# generic_maxi_1.net
KiCad netlist of a schematic drawn in EAGLE
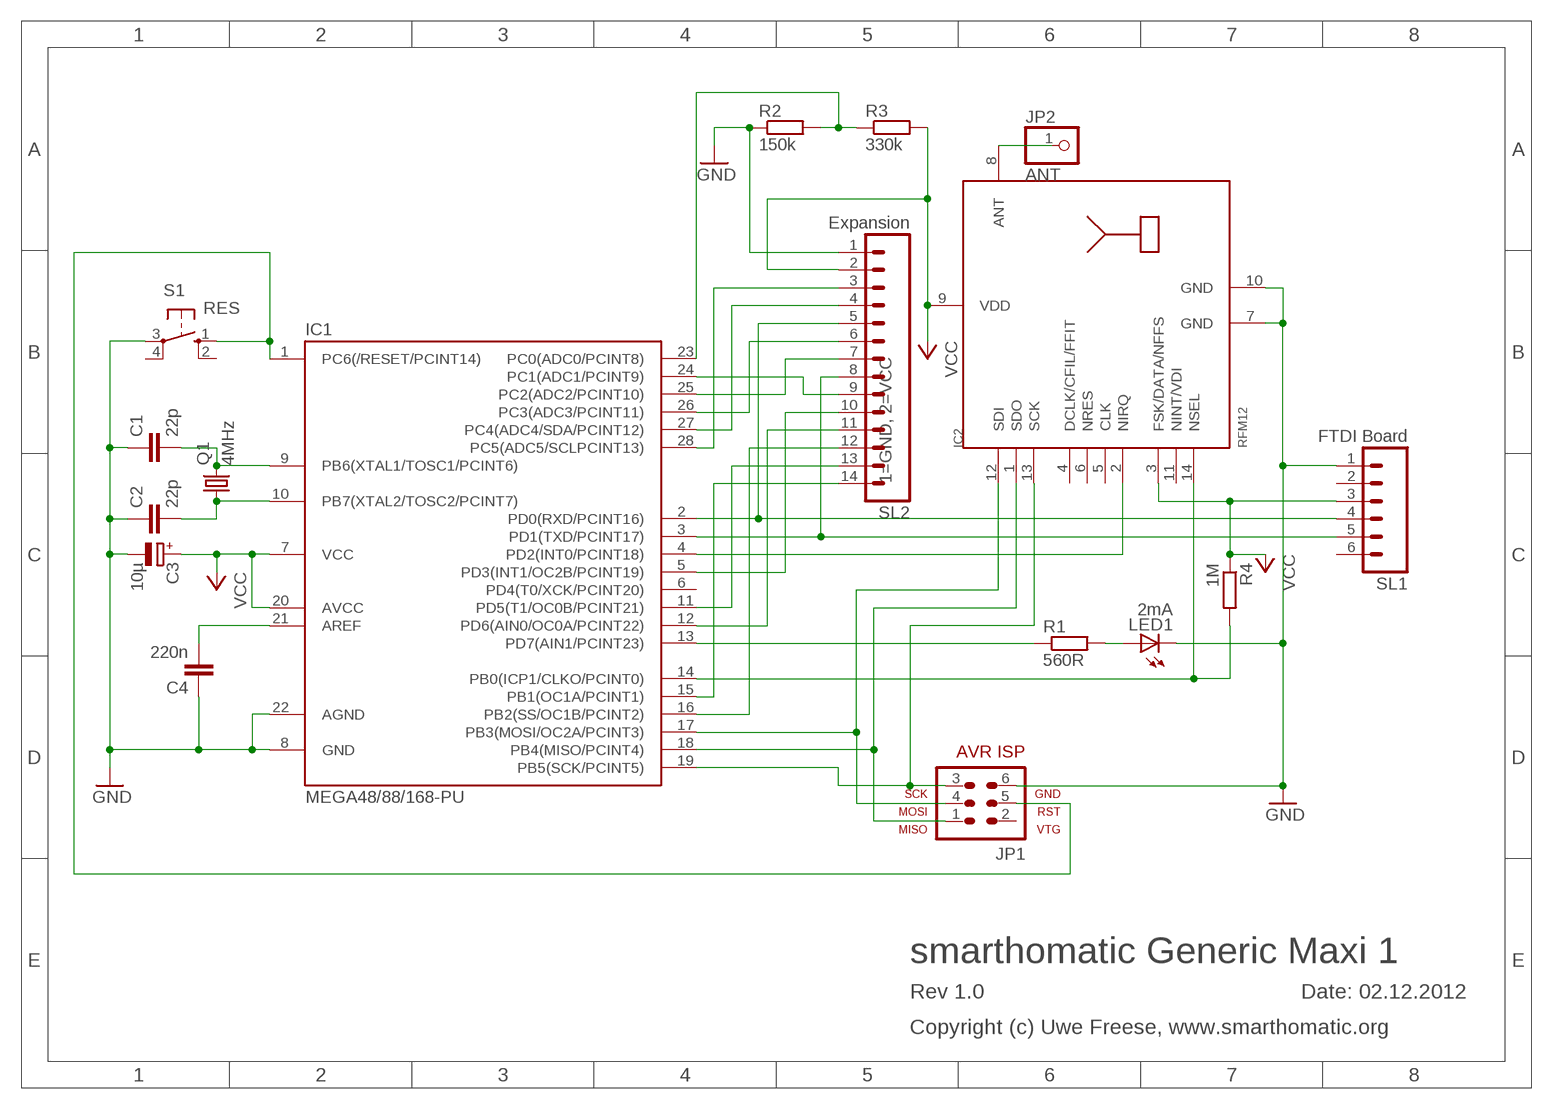
[diagram p0: schematic, sheet 1]

(export (version "E")
  (design (tool "Eeschema 10.0.6"))
  (components
    (comp (ref "C1")
      (value "22p")
      (footprint "eagle-import:C025-024X044")
      (libsource (lib "eagle-import") (part "C-EU025-024X044"))
    )
    (comp (ref "C2")
      (value "22p")
      (footprint "eagle-import:C025-024X044")
      (libsource (lib "eagle-import") (part "C-EU025-024X044"))
    )
    (comp (ref "C3")
      (value "10µ")
      (footprint "eagle-import:E1,8-4")
      (libsource (lib "eagle-import") (part "CPOL-EUE1.8-4"))
    )
    (comp (ref "C4")
      (value "220n")
      (footprint "eagle-import:C025-030X050")
      (libsource (lib "eagle-import") (part "C-EU025-030X050"))
    )
    (comp (ref "IC1")
      (value "MEGA48/88/168-PU")
      (footprint "eagle-import:DIL28-3")
      (libsource (lib "eagle-import") (part "MEGA48/88/168-PU"))
    )
    (comp (ref "IC2")
      (value "RFM12")
      (footprint "eagle-import:RFM")
      (libsource (lib "eagle-import") (part "RFM12"))
    )
    (comp (ref "JP1")
      (value "AVR-ISP-6")
      (footprint "eagle-import:AVR-ISP-6")
      (libsource (lib "eagle-import") (part "AVR-ISP-6"))
    )
    (comp (ref "JP2")
      (value "ANT")
      (footprint "eagle-import:1X01")
      (libsource (lib "eagle-import") (part "PINHD-1X1"))
    )
    (comp (ref "LED1")
      (value "2mA")
      (footprint "eagle-import:LED3MM")
      (libsource (lib "eagle-import") (part "LED3MM"))
    )
    (comp (ref "Q1")
      (value "4MHz")
      (footprint "eagle-import:HC49_S")
      (libsource (lib "eagle-import") (part "CRYSTALHC49S"))
    )
    (comp (ref "R1")
      (value "560R")
      (footprint "eagle-import:0207_7")
      (libsource (lib "eagle-import") (part "R-EU_0207/7"))
    )
    (comp (ref "R2")
      (value "150k")
      (footprint "eagle-import:0207_7")
      (libsource (lib "eagle-import") (part "R-EU_0207/7"))
    )
    (comp (ref "R3")
      (value "330k")
      (footprint "eagle-import:0207_7")
      (libsource (lib "eagle-import") (part "R-EU_0207/7"))
    )
    (comp (ref "R4")
      (value "1M")
      (footprint "eagle-import:0207_7")
      (libsource (lib "eagle-import") (part "R-EU_0207/7"))
    )
    (comp (ref "S1")
      (value "RES")
      (footprint "eagle-import:B3F-10XX")
      (fields (field (name "MPN") "B3F-1000"))
      (libsource (lib "eagle-import") (part "10-XX"))
    )
    (comp (ref "SL1")
      (value "FTDI Board")
      (footprint "eagle-import:06P")
      (libsource (lib "eagle-import") (part "M06"))
    )
    (comp (ref "SL2")
      (value "Expansion")
      (footprint "eagle-import:14P")
      (libsource (lib "eagle-import") (part "M14"))
    )
  )
  (nets
    (net (code "1") (name "GND") (class "Default")
      (node (ref "C1") (pin "1") (pinfunction "1_1") (pintype "passive"))
      (node (ref "C2") (pin "1") (pinfunction "1_1") (pintype "passive"))
      (node (ref "C3") (pin "-") (pinfunction "-_-") (pintype "passive"))
      (node (ref "C4") (pin "1") (pinfunction "1_1") (pintype "passive"))
      (node (ref "IC1") (pin "22") (pinfunction "AGND_22") (pintype "power_in"))
      (node (ref "IC1") (pin "8") (pinfunction "GND_8") (pintype "power_in"))
      (node (ref "IC2") (pin "10") (pinfunction "GND_10") (pintype "power_in"))
      (node (ref "IC2") (pin "7") (pinfunction "GND_7") (pintype "power_in"))
      (node (ref "JP1") (pin "6") (pinfunction "6_6") (pintype "passive"))
      (node (ref "LED1") (pin "K") (pinfunction "C_K") (pintype "passive"))
      (node (ref "R2") (pin "1") (pinfunction "1_1") (pintype "passive"))
      (node (ref "S1") (pin "3") (pinfunction "P_3") (pintype "passive"))
      (node (ref "SL1") (pin "1") (pinfunction "1_1") (pintype "passive"))
      (node (ref "SL2") (pin "1") (pinfunction "1_1") (pintype "passive"))
    )
    (net (code "2") (name "Net-(IC1-AREF)") (class "Default")
      (node (ref "C4") (pin "2") (pinfunction "2_2") (pintype "passive"))
      (node (ref "IC1") (pin "21") (pinfunction "AREF_21") (pintype "passive"))
    )
    (net (code "3") (name "Net-(IC1-PB0(ICP1{slash}CLKO{slash}PCINT0))") (class "Default")
      (node (ref "IC1") (pin "14") (pinfunction "PB0(ICP1/CLKO/PCINT0)_14") (pintype "bidirectional"))
      (node (ref "IC2") (pin "14") (pinfunction "NSEL_14") (pintype "bidirectional"))
      (node (ref "R4") (pin "2") (pinfunction "2_2") (pintype "passive"))
    )
    (net (code "4") (name "Net-(IC1-PB1(OC1A{slash}PCINT1))") (class "Default")
      (node (ref "IC1") (pin "15") (pinfunction "PB1(OC1A/PCINT1)_15") (pintype "bidirectional"))
      (node (ref "SL2") (pin "14") (pinfunction "14_14") (pintype "passive"))
    )
    (net (code "5") (name "Net-(IC1-PB2(SS{slash}OC1B{slash}PCINT2))") (class "Default")
      (node (ref "IC1") (pin "16") (pinfunction "PB2(SS/OC1B/PCINT2)_16") (pintype "bidirectional"))
      (node (ref "SL2") (pin "12") (pinfunction "12_12") (pintype "passive"))
    )
    (net (code "6") (name "Net-(IC1-PB3(MOSI{slash}OC2A{slash}PCINT3))") (class "Default")
      (node (ref "IC1") (pin "17") (pinfunction "PB3(MOSI/OC2A/PCINT3)_17") (pintype "bidirectional"))
      (node (ref "IC2") (pin "12") (pinfunction "SDI_12") (pintype "bidirectional"))
      (node (ref "JP1") (pin "4") (pinfunction "4_4") (pintype "passive"))
    )
    (net (code "7") (name "Net-(IC1-PB4(MISO{slash}PCINT4))") (class "Default")
      (node (ref "IC1") (pin "18") (pinfunction "PB4(MISO/PCINT4)_18") (pintype "bidirectional"))
      (node (ref "IC2") (pin "1") (pinfunction "SDO_1") (pintype "bidirectional"))
      (node (ref "JP1") (pin "1") (pinfunction "1_1") (pintype "passive"))
    )
    (net (code "8") (name "Net-(IC1-PB5(SCK{slash}PCINT5))") (class "Default")
      (node (ref "IC1") (pin "19") (pinfunction "PB5(SCK/PCINT5)_19") (pintype "bidirectional"))
      (node (ref "IC2") (pin "13") (pinfunction "SCK_13") (pintype "bidirectional"))
      (node (ref "JP1") (pin "3") (pinfunction "3_3") (pintype "passive"))
    )
    (net (code "9") (name "Net-(IC1-PB6(XTAL1{slash}TOSC1{slash}PCINT6))") (class "Default")
      (node (ref "C1") (pin "2") (pinfunction "2_2") (pintype "passive"))
      (node (ref "IC1") (pin "9") (pinfunction "PB6(XTAL1/TOSC1/PCINT6)_9") (pintype "bidirectional"))
      (node (ref "Q1") (pin "2") (pinfunction "2_2") (pintype "passive"))
    )
    (net (code "10") (name "Net-(IC1-PB7(XTAL2{slash}TOSC2{slash}PCINT7))") (class "Default")
      (node (ref "C2") (pin "2") (pinfunction "2_2") (pintype "passive"))
      (node (ref "IC1") (pin "10") (pinfunction "PB7(XTAL2/TOSC2/PCINT7)_10") (pintype "bidirectional"))
      (node (ref "Q1") (pin "1") (pinfunction "1_1") (pintype "passive"))
    )
    (net (code "11") (name "Net-(IC1-PC0(ADC0{slash}PCINT8))") (class "Default")
      (node (ref "IC1") (pin "23") (pinfunction "PC0(ADC0/PCINT8)_23") (pintype "bidirectional"))
      (node (ref "R2") (pin "2") (pinfunction "2_2") (pintype "passive"))
      (node (ref "R3") (pin "1") (pinfunction "1_1") (pintype "passive"))
    )
    (net (code "12") (name "Net-(IC1-PC1(ADC1{slash}PCINT9))") (class "Default")
      (node (ref "IC1") (pin "24") (pinfunction "PC1(ADC1/PCINT9)_24") (pintype "bidirectional"))
      (node (ref "SL2") (pin "9") (pinfunction "9_9") (pintype "passive"))
    )
    (net (code "13") (name "Net-(IC1-PC2(ADC2{slash}PCINT10))") (class "Default")
      (node (ref "IC1") (pin "25") (pinfunction "PC2(ADC2/PCINT10)_25") (pintype "bidirectional"))
      (node (ref "SL2") (pin "7") (pinfunction "7_7") (pintype "passive"))
    )
    (net (code "14") (name "Net-(IC1-PC3(ADC3{slash}PCINT11))") (class "Default")
      (node (ref "IC1") (pin "26") (pinfunction "PC3(ADC3/PCINT11)_26") (pintype "bidirectional"))
      (node (ref "SL2") (pin "6") (pinfunction "6_6") (pintype "passive"))
    )
    (net (code "15") (name "Net-(IC1-PC4(ADC4{slash}SDA{slash}PCINT12))") (class "Default")
      (node (ref "IC1") (pin "27") (pinfunction "PC4(ADC4/SDA/PCINT12)_27") (pintype "bidirectional"))
      (node (ref "SL2") (pin "4") (pinfunction "4_4") (pintype "passive"))
    )
    (net (code "16") (name "Net-(IC1-PC5(ADC5{slash}SCLPCINT13))") (class "Default")
      (node (ref "IC1") (pin "28") (pinfunction "PC5(ADC5/SCLPCINT13)_28") (pintype "bidirectional"))
      (node (ref "SL2") (pin "3") (pinfunction "3_3") (pintype "passive"))
    )
    (net (code "17") (name "Net-(IC1-PC6({slash}RESET{slash}PCINT14))") (class "Default")
      (node (ref "IC1") (pin "1") (pinfunction "PC6(/RESET/PCINT14)_1") (pintype "bidirectional"))
      (node (ref "JP1") (pin "5") (pinfunction "5_5") (pintype "passive"))
      (node (ref "S1") (pin "1") (pinfunction "S_1") (pintype "passive"))
    )
    (net (code "18") (name "Net-(IC1-PD0(RXD{slash}PCINT16))") (class "Default")
      (node (ref "IC1") (pin "2") (pinfunction "PD0(RXD/PCINT16)_2") (pintype "bidirectional"))
      (node (ref "SL1") (pin "4") (pinfunction "4_4") (pintype "passive"))
      (node (ref "SL2") (pin "5") (pinfunction "5_5") (pintype "passive"))
    )
    (net (code "19") (name "Net-(IC1-PD1(TXD{slash}PCINT17))") (class "Default")
      (node (ref "IC1") (pin "3") (pinfunction "PD1(TXD/PCINT17)_3") (pintype "bidirectional"))
      (node (ref "SL1") (pin "5") (pinfunction "5_5") (pintype "passive"))
      (node (ref "SL2") (pin "8") (pinfunction "8_8") (pintype "passive"))
    )
    (net (code "20") (name "Net-(IC1-PD2(INT0{slash}PCINT18))") (class "Default")
      (node (ref "IC1") (pin "4") (pinfunction "PD2(INT0/PCINT18)_4") (pintype "bidirectional"))
      (node (ref "IC2") (pin "2") (pinfunction "NIRQ_2") (pintype "bidirectional"))
    )
    (net (code "21") (name "Net-(IC1-PD3(INT1{slash}OC2B{slash}PCINT19))") (class "Default")
      (node (ref "IC1") (pin "5") (pinfunction "PD3(INT1/OC2B/PCINT19)_5") (pintype "bidirectional"))
      (node (ref "SL2") (pin "10") (pinfunction "10_10") (pintype "passive"))
    )
    (net (code "22") (name "Net-(IC1-PD5(T1{slash}OC0B{slash}PCINT21))") (class "Default")
      (node (ref "IC1") (pin "11") (pinfunction "PD5(T1/OC0B/PCINT21)_11") (pintype "bidirectional"))
      (node (ref "SL2") (pin "13") (pinfunction "13_13") (pintype "passive"))
    )
    (net (code "23") (name "Net-(IC1-PD6(AIN0{slash}OC0A{slash}PCINT22))") (class "Default")
      (node (ref "IC1") (pin "12") (pinfunction "PD6(AIN0/OC0A/PCINT22)_12") (pintype "bidirectional"))
      (node (ref "SL2") (pin "11") (pinfunction "11_11") (pintype "passive"))
    )
    (net (code "24") (name "Net-(IC1-PD7(AIN1{slash}PCINT23))") (class "Default")
      (node (ref "IC1") (pin "13") (pinfunction "PD7(AIN1/PCINT23)_13") (pintype "bidirectional"))
      (node (ref "R1") (pin "1") (pinfunction "1_1") (pintype "passive"))
    )
    (net (code "25") (name "Net-(IC2-ANT)") (class "Default")
      (node (ref "IC2") (pin "8") (pinfunction "ANT_8") (pintype "output"))
      (node (ref "JP2") (pin "1") (pinfunction "1_1") (pintype "passive"))
    )
    (net (code "26") (name "Net-(LED1-PadA)") (class "Default")
      (node (ref "LED1") (pin "A") (pinfunction "A_A") (pintype "passive"))
      (node (ref "R1") (pin "2") (pinfunction "2_2") (pintype "passive"))
    )
    (net (code "27") (name "VCC") (class "Default")
      (node (ref "C3") (pin "+") (pinfunction "+_+") (pintype "passive"))
      (node (ref "IC1") (pin "20") (pinfunction "AVCC_20") (pintype "passive"))
      (node (ref "IC1") (pin "7") (pinfunction "VCC_7") (pintype "power_in"))
      (node (ref "IC2") (pin "3") (pinfunction "FSK/DATA/NFFS_3") (pintype "bidirectional"))
      (node (ref "IC2") (pin "9") (pinfunction "VDD_9") (pintype "power_in"))
      (node (ref "R3") (pin "2") (pinfunction "2_2") (pintype "passive"))
      (node (ref "R4") (pin "1") (pinfunction "1_1") (pintype "passive"))
      (node (ref "SL1") (pin "3") (pinfunction "3_3") (pintype "passive"))
      (node (ref "SL2") (pin "2") (pinfunction "2_2") (pintype "passive"))
    )
    (net (code "28") (name "unconnected-(IC1-PD4(T0{slash}XCK{slash}PCINT20)-Pad6)") (class "Default")
      (node (ref "IC1") (pin "6") (pinfunction "PD4(T0/XCK/PCINT20)_6") (pintype "bidirectional"))
    )
    (net (code "29") (name "unconnected-(IC2-CLK-Pad5)") (class "Default")
      (node (ref "IC2") (pin "5") (pinfunction "CLK_5") (pintype "bidirectional"))
    )
    (net (code "30") (name "unconnected-(IC2-DCLK{slash}CFIL{slash}FFIT-Pad4)") (class "Default")
      (node (ref "IC2") (pin "4") (pinfunction "DCLK/CFIL/FFIT_4") (pintype "bidirectional"))
    )
    (net (code "31") (name "unconnected-(IC2-NINT{slash}VDI-Pad11)") (class "Default")
      (node (ref "IC2") (pin "11") (pinfunction "NINT/VDI_11") (pintype "bidirectional"))
    )
    (net (code "32") (name "unconnected-(IC2-NRES-Pad6)") (class "Default")
      (node (ref "IC2") (pin "6") (pinfunction "NRES_6") (pintype "bidirectional"))
    )
    (net (code "33") (name "unconnected-(JP1-Pad2)") (class "Default")
      (node (ref "JP1") (pin "2") (pinfunction "2_2") (pintype "passive"))
    )
    (net (code "34") (name "unconnected-(S1-P1-Pad4)") (class "Default")
      (node (ref "S1") (pin "4") (pinfunction "P1_4") (pintype "passive"))
    )
    (net (code "35") (name "unconnected-(S1-S1-Pad2)") (class "Default")
      (node (ref "S1") (pin "2") (pinfunction "S1_2") (pintype "passive"))
    )
    (net (code "36") (name "unconnected-(SL1-Pad2)") (class "Default")
      (node (ref "SL1") (pin "2") (pinfunction "2_2") (pintype "passive"))
    )
    (net (code "37") (name "unconnected-(SL1-Pad6)") (class "Default")
      (node (ref "SL1") (pin "6") (pinfunction "6_6") (pintype "passive"))
    )
  )
)
